# PomodoroClock.net
KiCad netlist of a schematic drawn in EAGLE
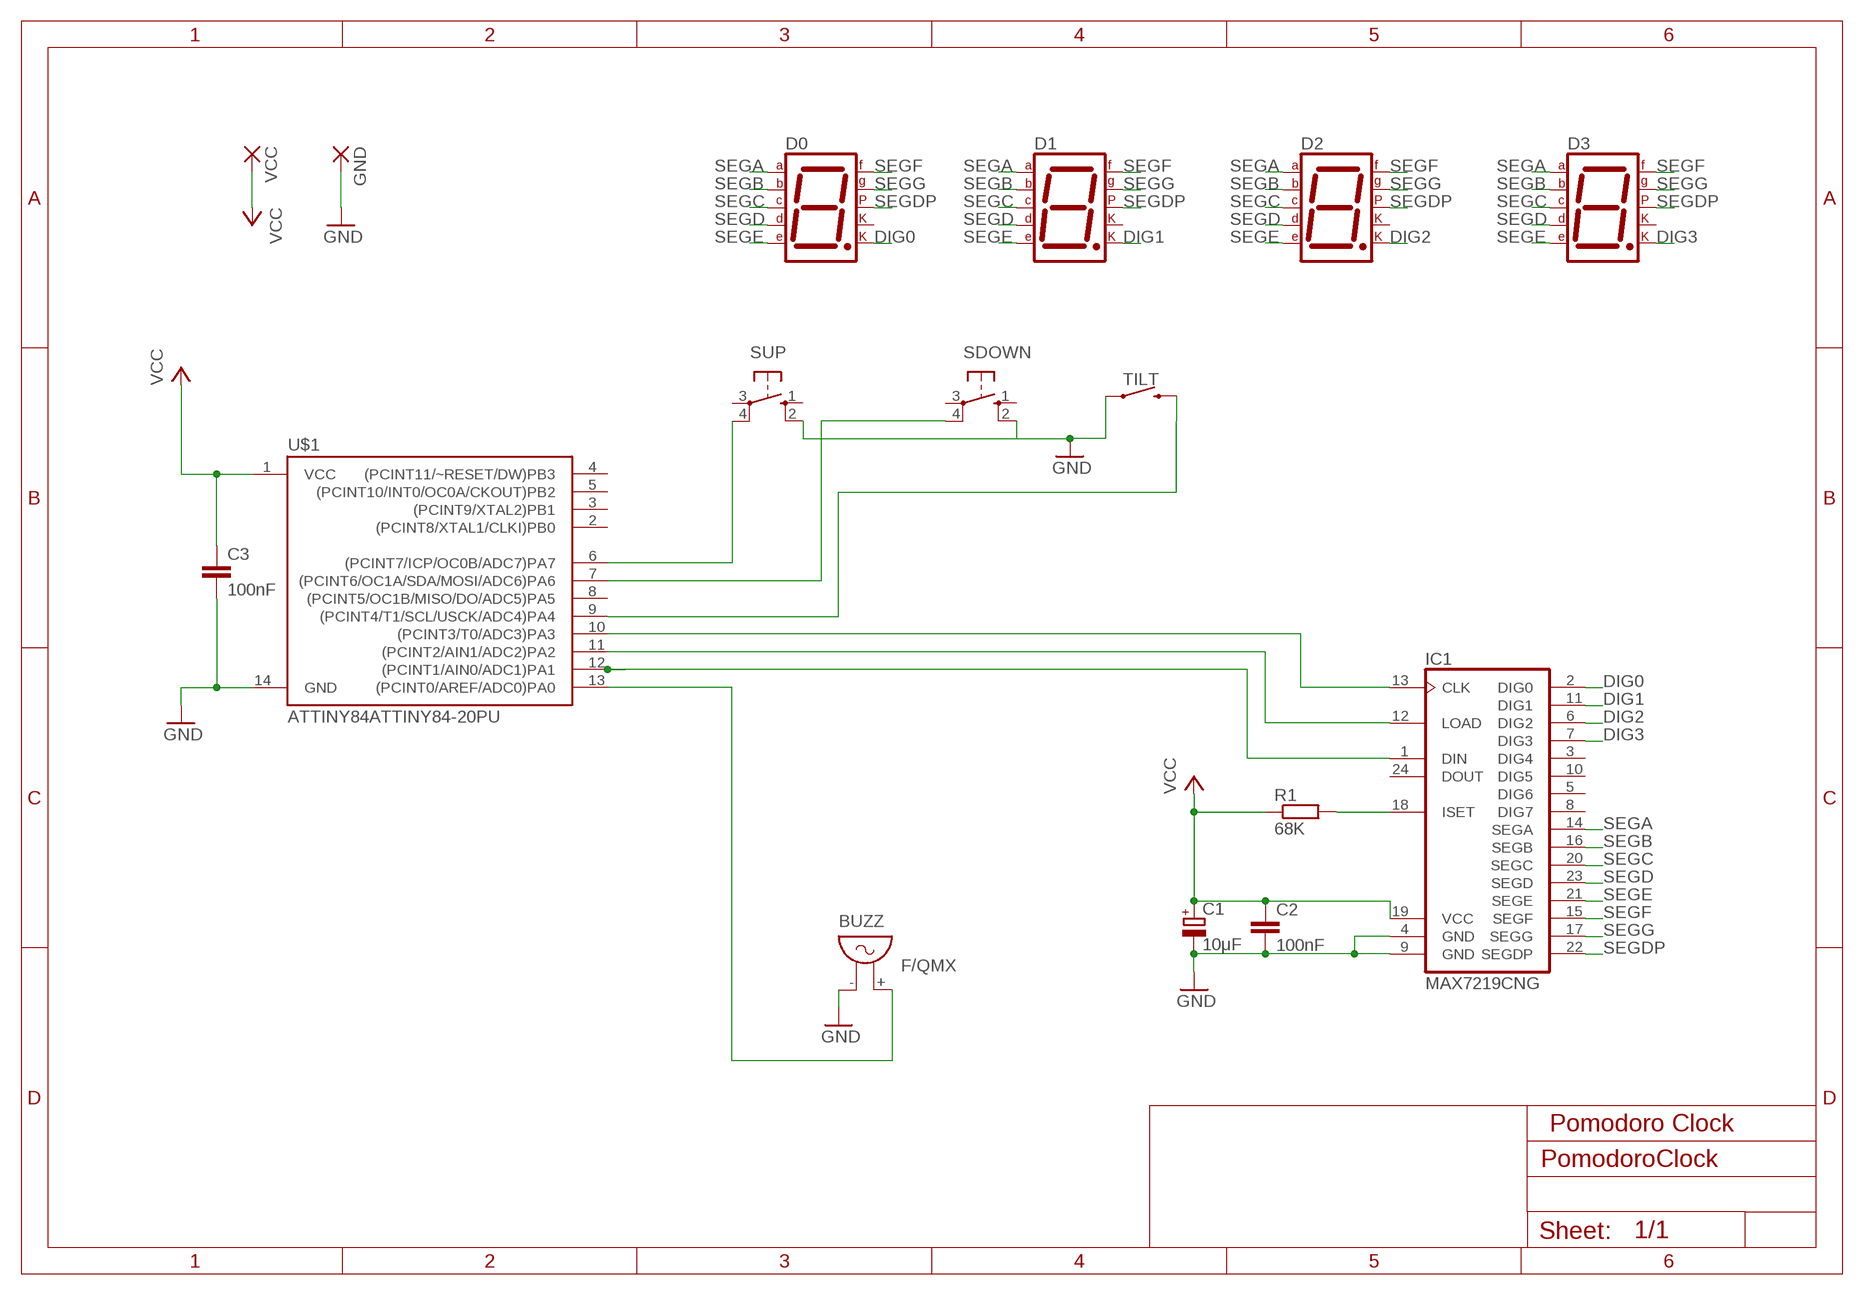
[diagram p0: schematic, sheet 1]

(export (version "E")
  (design (tool "Eeschema 10.0.6"))
  (components
    (comp (ref "BUZZ")
      (value "F/QMX")
      (footprint "eagle-import:F_QMX")
      (libsource (lib "eagle-import") (part "F/QMX"))
    )
    (comp (ref "C1")
      (value "10μF")
      (footprint "eagle-import:E2,5-6E")
      (libsource (lib "eagle-import") (part "CPOL-EUE2,5-6E"))
    )
    (comp (ref "C2")
      (value "100nF")
      (footprint "eagle-import:C025-025X050")
      (libsource (lib "eagle-import") (part "C-EU025-025X050"))
    )
    (comp (ref "C3")
      (value "100nF")
      (footprint "eagle-import:C025-025X050")
      (libsource (lib "eagle-import") (part "C-EU025-025X050"))
    )
    (comp (ref "D0")
      (value "7SEG-CK")
      (footprint "eagle-import:7SEG-13")
      (libsource (lib "eagle-import") (part "7SEG-CK"))
    )
    (comp (ref "D1")
      (value "7SEG-CK")
      (footprint "eagle-import:7SEG-13")
      (libsource (lib "eagle-import") (part "7SEG-CK"))
    )
    (comp (ref "D2")
      (value "7SEG-CK")
      (footprint "eagle-import:7SEG-13")
      (libsource (lib "eagle-import") (part "7SEG-CK"))
    )
    (comp (ref "D3")
      (value "7SEG-CK")
      (footprint "eagle-import:7SEG-13")
      (libsource (lib "eagle-import") (part "7SEG-CK"))
    )
    (comp (ref "GND")
      (value "3,81/1,4")
      (footprint "eagle-import:3,81_1,4")
      (libsource (lib "eagle-import") (part "3,81/1,4"))
    )
    (comp (ref "IC1")
      (value "MAX7219CNG")
      (footprint "eagle-import:DIL24-3")
      (fields (field (name "MF") "MAXIM"))
      (libsource (lib "eagle-import") (part "MAX7219CNG"))
    )
    (comp (ref "R1")
      (value "68K")
      (footprint "eagle-import:0207_10")
      (libsource (lib "eagle-import") (part "R-EU_0207/10"))
    )
    (comp (ref "SDOWN")
      (value "10-XX")
      (footprint "eagle-import:B3F-10XX")
      (fields (field (name "MPN") "B3F-1000"))
      (libsource (lib "eagle-import") (part "10-XX"))
    )
    (comp (ref "SUP")
      (value "10-XX")
      (footprint "eagle-import:B3F-10XX")
      (fields (field (name "MPN") "B3F-1000"))
      (libsource (lib "eagle-import") (part "10-XX"))
    )
    (comp (ref "TILT")
      (value "TILT")
      (footprint "eagle-import:TILT")
      (libsource (lib "eagle-import") (part "TILT"))
    )
    (comp (ref "U$1")
      (value "ATTINY84ATTINY84-20PU")
      (footprint "eagle-import:DIP14")
      (libsource (lib "eagle-import") (part "ATTINY84ATTINY84-20PU"))
    )
    (comp (ref "VCC")
      (value "3,81/1,4")
      (footprint "eagle-import:3,81_1,4")
      (libsource (lib "eagle-import") (part "3,81/1,4"))
    )
  )
  (nets
    (net (code "1") (name "/DIG0") (class "Default")
      (node (ref "D0") (pin "8") (pinfunction "CK2_8") (pintype "passive"))
      (node (ref "IC1") (pin "2") (pinfunction "DIG0_2") (pintype "output"))
    )
    (net (code "2") (name "/DIG1") (class "Default")
      (node (ref "D1") (pin "8") (pinfunction "CK2_8") (pintype "passive"))
      (node (ref "IC1") (pin "11") (pinfunction "DIG1_11") (pintype "output"))
    )
    (net (code "3") (name "/DIG2") (class "Default")
      (node (ref "D2") (pin "8") (pinfunction "CK2_8") (pintype "passive"))
      (node (ref "IC1") (pin "6") (pinfunction "DIG2_6") (pintype "output"))
    )
    (net (code "4") (name "/DIG3") (class "Default")
      (node (ref "D3") (pin "8") (pinfunction "CK2_8") (pintype "passive"))
      (node (ref "IC1") (pin "7") (pinfunction "DIG3_7") (pintype "output"))
    )
    (net (code "5") (name "/SEGA") (class "Default")
      (node (ref "D0") (pin "7") (pinfunction "A_7") (pintype "passive"))
      (node (ref "D1") (pin "7") (pinfunction "A_7") (pintype "passive"))
      (node (ref "D2") (pin "7") (pinfunction "A_7") (pintype "passive"))
      (node (ref "D3") (pin "7") (pinfunction "A_7") (pintype "passive"))
      (node (ref "IC1") (pin "14") (pinfunction "SEGA_14") (pintype "output"))
    )
    (net (code "6") (name "/SEGB") (class "Default")
      (node (ref "D0") (pin "6") (pinfunction "B_6") (pintype "passive"))
      (node (ref "D1") (pin "6") (pinfunction "B_6") (pintype "passive"))
      (node (ref "D2") (pin "6") (pinfunction "B_6") (pintype "passive"))
      (node (ref "D3") (pin "6") (pinfunction "B_6") (pintype "passive"))
      (node (ref "IC1") (pin "16") (pinfunction "SEGB_16") (pintype "output"))
    )
    (net (code "7") (name "/SEGC") (class "Default")
      (node (ref "D0") (pin "4") (pinfunction "C_4") (pintype "passive"))
      (node (ref "D1") (pin "4") (pinfunction "C_4") (pintype "passive"))
      (node (ref "D2") (pin "4") (pinfunction "C_4") (pintype "passive"))
      (node (ref "D3") (pin "4") (pinfunction "C_4") (pintype "passive"))
      (node (ref "IC1") (pin "20") (pinfunction "SEGC_20") (pintype "output"))
    )
    (net (code "8") (name "/SEGD") (class "Default")
      (node (ref "D0") (pin "2") (pinfunction "D_2") (pintype "passive"))
      (node (ref "D1") (pin "2") (pinfunction "D_2") (pintype "passive"))
      (node (ref "D2") (pin "2") (pinfunction "D_2") (pintype "passive"))
      (node (ref "D3") (pin "2") (pinfunction "D_2") (pintype "passive"))
      (node (ref "IC1") (pin "23") (pinfunction "SEGD_23") (pintype "output"))
    )
    (net (code "9") (name "/SEGDP") (class "Default")
      (node (ref "D0") (pin "5") (pinfunction "DP_5") (pintype "passive"))
      (node (ref "D1") (pin "5") (pinfunction "DP_5") (pintype "passive"))
      (node (ref "D2") (pin "5") (pinfunction "DP_5") (pintype "passive"))
      (node (ref "D3") (pin "5") (pinfunction "DP_5") (pintype "passive"))
      (node (ref "IC1") (pin "22") (pinfunction "SEGDP_22") (pintype "output"))
    )
    (net (code "10") (name "/SEGE") (class "Default")
      (node (ref "D0") (pin "1") (pinfunction "E_1") (pintype "passive"))
      (node (ref "D1") (pin "1") (pinfunction "E_1") (pintype "passive"))
      (node (ref "D2") (pin "1") (pinfunction "E_1") (pintype "passive"))
      (node (ref "D3") (pin "1") (pinfunction "E_1") (pintype "passive"))
      (node (ref "IC1") (pin "21") (pinfunction "SEGE_21") (pintype "output"))
    )
    (net (code "11") (name "/SEGF") (class "Default")
      (node (ref "D0") (pin "9") (pinfunction "F_9") (pintype "passive"))
      (node (ref "D1") (pin "9") (pinfunction "F_9") (pintype "passive"))
      (node (ref "D2") (pin "9") (pinfunction "F_9") (pintype "passive"))
      (node (ref "D3") (pin "9") (pinfunction "F_9") (pintype "passive"))
      (node (ref "IC1") (pin "15") (pinfunction "SEGF_15") (pintype "output"))
    )
    (net (code "12") (name "/SEGG") (class "Default")
      (node (ref "D0") (pin "10") (pinfunction "G_10") (pintype "passive"))
      (node (ref "D1") (pin "10") (pinfunction "G_10") (pintype "passive"))
      (node (ref "D2") (pin "10") (pinfunction "G_10") (pintype "passive"))
      (node (ref "D3") (pin "10") (pinfunction "G_10") (pintype "passive"))
      (node (ref "IC1") (pin "17") (pinfunction "SEGG_17") (pintype "output"))
    )
    (net (code "13") (name "GND") (class "Default")
      (node (ref "BUZZ") (pin "-") (pinfunction "1_-") (pintype "passive"))
      (node (ref "C1") (pin "-") (pinfunction "-_-") (pintype "passive"))
      (node (ref "C2") (pin "2") (pinfunction "2_2") (pintype "passive"))
      (node (ref "C3") (pin "2") (pinfunction "2_2") (pintype "passive"))
      (node (ref "GND") (pin "1") (pinfunction "P_1") (pintype "passive"))
      (node (ref "IC1") (pin "4") (pinfunction "GND_4") (pintype "power_in"))
      (node (ref "IC1") (pin "9") (pinfunction "GND_9") (pintype "power_in"))
      (node (ref "SDOWN") (pin "2") (pinfunction "S1_2") (pintype "passive"))
      (node (ref "SUP") (pin "2") (pinfunction "S1_2") (pintype "passive"))
      (node (ref "TILT") (pin "1") (pinfunction "3_1") (pintype "passive"))
      (node (ref "U$1") (pin "14") (pinfunction "GND_14") (pintype "bidirectional"))
    )
    (net (code "14") (name "Net-(BUZZ-2)") (class "Default")
      (node (ref "BUZZ") (pin "+") (pinfunction "2_+") (pintype "passive"))
      (node (ref "U$1") (pin "13") (pinfunction "(PCINT0/AREF/ADC0)PA0_13") (pintype "bidirectional"))
    )
    (net (code "15") (name "Net-(IC1-CLK)") (class "Default")
      (node (ref "IC1") (pin "13") (pinfunction "CLK_13") (pintype "input"))
      (node (ref "U$1") (pin "10") (pinfunction "(PCINT3/T0/ADC3)PA3_10") (pintype "bidirectional"))
    )
    (net (code "16") (name "Net-(IC1-DIN)") (class "Default")
      (node (ref "IC1") (pin "1") (pinfunction "DIN_1") (pintype "input"))
      (node (ref "U$1") (pin "12") (pinfunction "(PCINT1/AIN0/ADC1)PA1_12") (pintype "bidirectional"))
    )
    (net (code "17") (name "Net-(IC1-ISET)") (class "Default")
      (node (ref "IC1") (pin "18") (pinfunction "ISET_18") (pintype "input"))
      (node (ref "R1") (pin "2") (pinfunction "2_2") (pintype "passive"))
    )
    (net (code "18") (name "Net-(IC1-LOAD)") (class "Default")
      (node (ref "IC1") (pin "12") (pinfunction "LOAD_12") (pintype "input"))
      (node (ref "U$1") (pin "11") (pinfunction "(PCINT2/AIN1/ADC2)PA2_11") (pintype "bidirectional"))
    )
    (net (code "19") (name "Net-(SDOWN-P1)") (class "Default")
      (node (ref "SDOWN") (pin "4") (pinfunction "P1_4") (pintype "passive"))
      (node (ref "U$1") (pin "7") (pinfunction "(PCINT6/OC1A/SDA/MOSI/ADC6)PA6_7") (pintype "bidirectional"))
    )
    (net (code "20") (name "Net-(SUP-P1)") (class "Default")
      (node (ref "SUP") (pin "4") (pinfunction "P1_4") (pintype "passive"))
      (node (ref "U$1") (pin "6") (pinfunction "(PCINT7/ICP/OC0B/ADC7)PA7_6") (pintype "bidirectional"))
    )
    (net (code "21") (name "Net-(TILT-4)") (class "Default")
      (node (ref "TILT") (pin "2") (pinfunction "4_2") (pintype "passive"))
      (node (ref "U$1") (pin "9") (pinfunction "(PCINT4/T1/SCL/USCK/ADC4)PA4_9") (pintype "bidirectional"))
    )
    (net (code "22") (name "VCC") (class "Default")
      (node (ref "C1") (pin "+") (pinfunction "+_+") (pintype "passive"))
      (node (ref "C2") (pin "1") (pinfunction "1_1") (pintype "passive"))
      (node (ref "C3") (pin "1") (pinfunction "1_1") (pintype "passive"))
      (node (ref "IC1") (pin "19") (pinfunction "VCC_19") (pintype "power_in"))
      (node (ref "R1") (pin "1") (pinfunction "1_1") (pintype "passive"))
      (node (ref "U$1") (pin "1") (pinfunction "VCC_1") (pintype "bidirectional"))
      (node (ref "VCC") (pin "1") (pinfunction "P_1") (pintype "passive"))
    )
    (net (code "23") (name "unconnected-(D0-CK1-Pad3)") (class "Default")
      (node (ref "D0") (pin "3") (pinfunction "CK1_3") (pintype "passive"))
    )
    (net (code "24") (name "unconnected-(D1-CK1-Pad3)") (class "Default")
      (node (ref "D1") (pin "3") (pinfunction "CK1_3") (pintype "passive"))
    )
    (net (code "25") (name "unconnected-(D2-CK1-Pad3)") (class "Default")
      (node (ref "D2") (pin "3") (pinfunction "CK1_3") (pintype "passive"))
    )
    (net (code "26") (name "unconnected-(D3-CK1-Pad3)") (class "Default")
      (node (ref "D3") (pin "3") (pinfunction "CK1_3") (pintype "passive"))
    )
    (net (code "27") (name "unconnected-(IC1-DIG4-Pad3)") (class "Default")
      (node (ref "IC1") (pin "3") (pinfunction "DIG4_3") (pintype "output"))
    )
    (net (code "28") (name "unconnected-(IC1-DIG5-Pad10)") (class "Default")
      (node (ref "IC1") (pin "10") (pinfunction "DIG5_10") (pintype "output"))
    )
    (net (code "29") (name "unconnected-(IC1-DIG6-Pad5)") (class "Default")
      (node (ref "IC1") (pin "5") (pinfunction "DIG6_5") (pintype "output"))
    )
    (net (code "30") (name "unconnected-(IC1-DIG7-Pad8)") (class "Default")
      (node (ref "IC1") (pin "8") (pinfunction "DIG7_8") (pintype "output"))
    )
    (net (code "31") (name "unconnected-(IC1-DOUT-Pad24)") (class "Default")
      (node (ref "IC1") (pin "24") (pinfunction "DOUT_24") (pintype "output"))
    )
    (net (code "32") (name "unconnected-(SDOWN-P-Pad3)") (class "Default")
      (node (ref "SDOWN") (pin "3") (pinfunction "P_3") (pintype "passive"))
    )
    (net (code "33") (name "unconnected-(SDOWN-S-Pad1)") (class "Default")
      (node (ref "SDOWN") (pin "1") (pinfunction "S_1") (pintype "passive"))
    )
    (net (code "34") (name "unconnected-(SUP-P-Pad3)") (class "Default")
      (node (ref "SUP") (pin "3") (pinfunction "P_3") (pintype "passive"))
    )
    (net (code "35") (name "unconnected-(SUP-S-Pad1)") (class "Default")
      (node (ref "SUP") (pin "1") (pinfunction "S_1") (pintype "passive"))
    )
    (net (code "36") (name "unconnected-(U$1-(PCINT5{slash}OC1B{slash}MISO{slash}DO{slash}ADC5)PA5-Pad8)") (class "Default")
      (node (ref "U$1") (pin "8") (pinfunction "(PCINT5/OC1B/MISO/DO/ADC5)PA5_8") (pintype "bidirectional"))
    )
    (net (code "37") (name "unconnected-(U$1-(PCINT8{slash}XTAL1{slash}CLKI)PB0-Pad2)") (class "Default")
      (node (ref "U$1") (pin "2") (pinfunction "(PCINT8/XTAL1/CLKI)PB0_2") (pintype "bidirectional"))
    )
    (net (code "38") (name "unconnected-(U$1-(PCINT9{slash}XTAL2)PB1-Pad3)") (class "Default")
      (node (ref "U$1") (pin "3") (pinfunction "(PCINT9/XTAL2)PB1_3") (pintype "bidirectional"))
    )
    (net (code "39") (name "unconnected-(U$1-(PCINT10{slash}INT0{slash}OC0A{slash}CKOUT)PB2-Pad5)") (class "Default")
      (node (ref "U$1") (pin "5") (pinfunction "(PCINT10/INT0/OC0A/CKOUT)PB2_5") (pintype "bidirectional"))
    )
    (net (code "40") (name "unconnected-(U$1-(PCINT11{slash}~{RESET{slash}DW})PB3-Pad4)") (class "Default")
      (node (ref "U$1") (pin "4") (pinfunction "(PCINT11/~{RESET/DW})PB3_4") (pintype "bidirectional"))
    )
  )
)
